# RTM_CON.net
KiCad netlist of a schematic drawn in Altium Designer
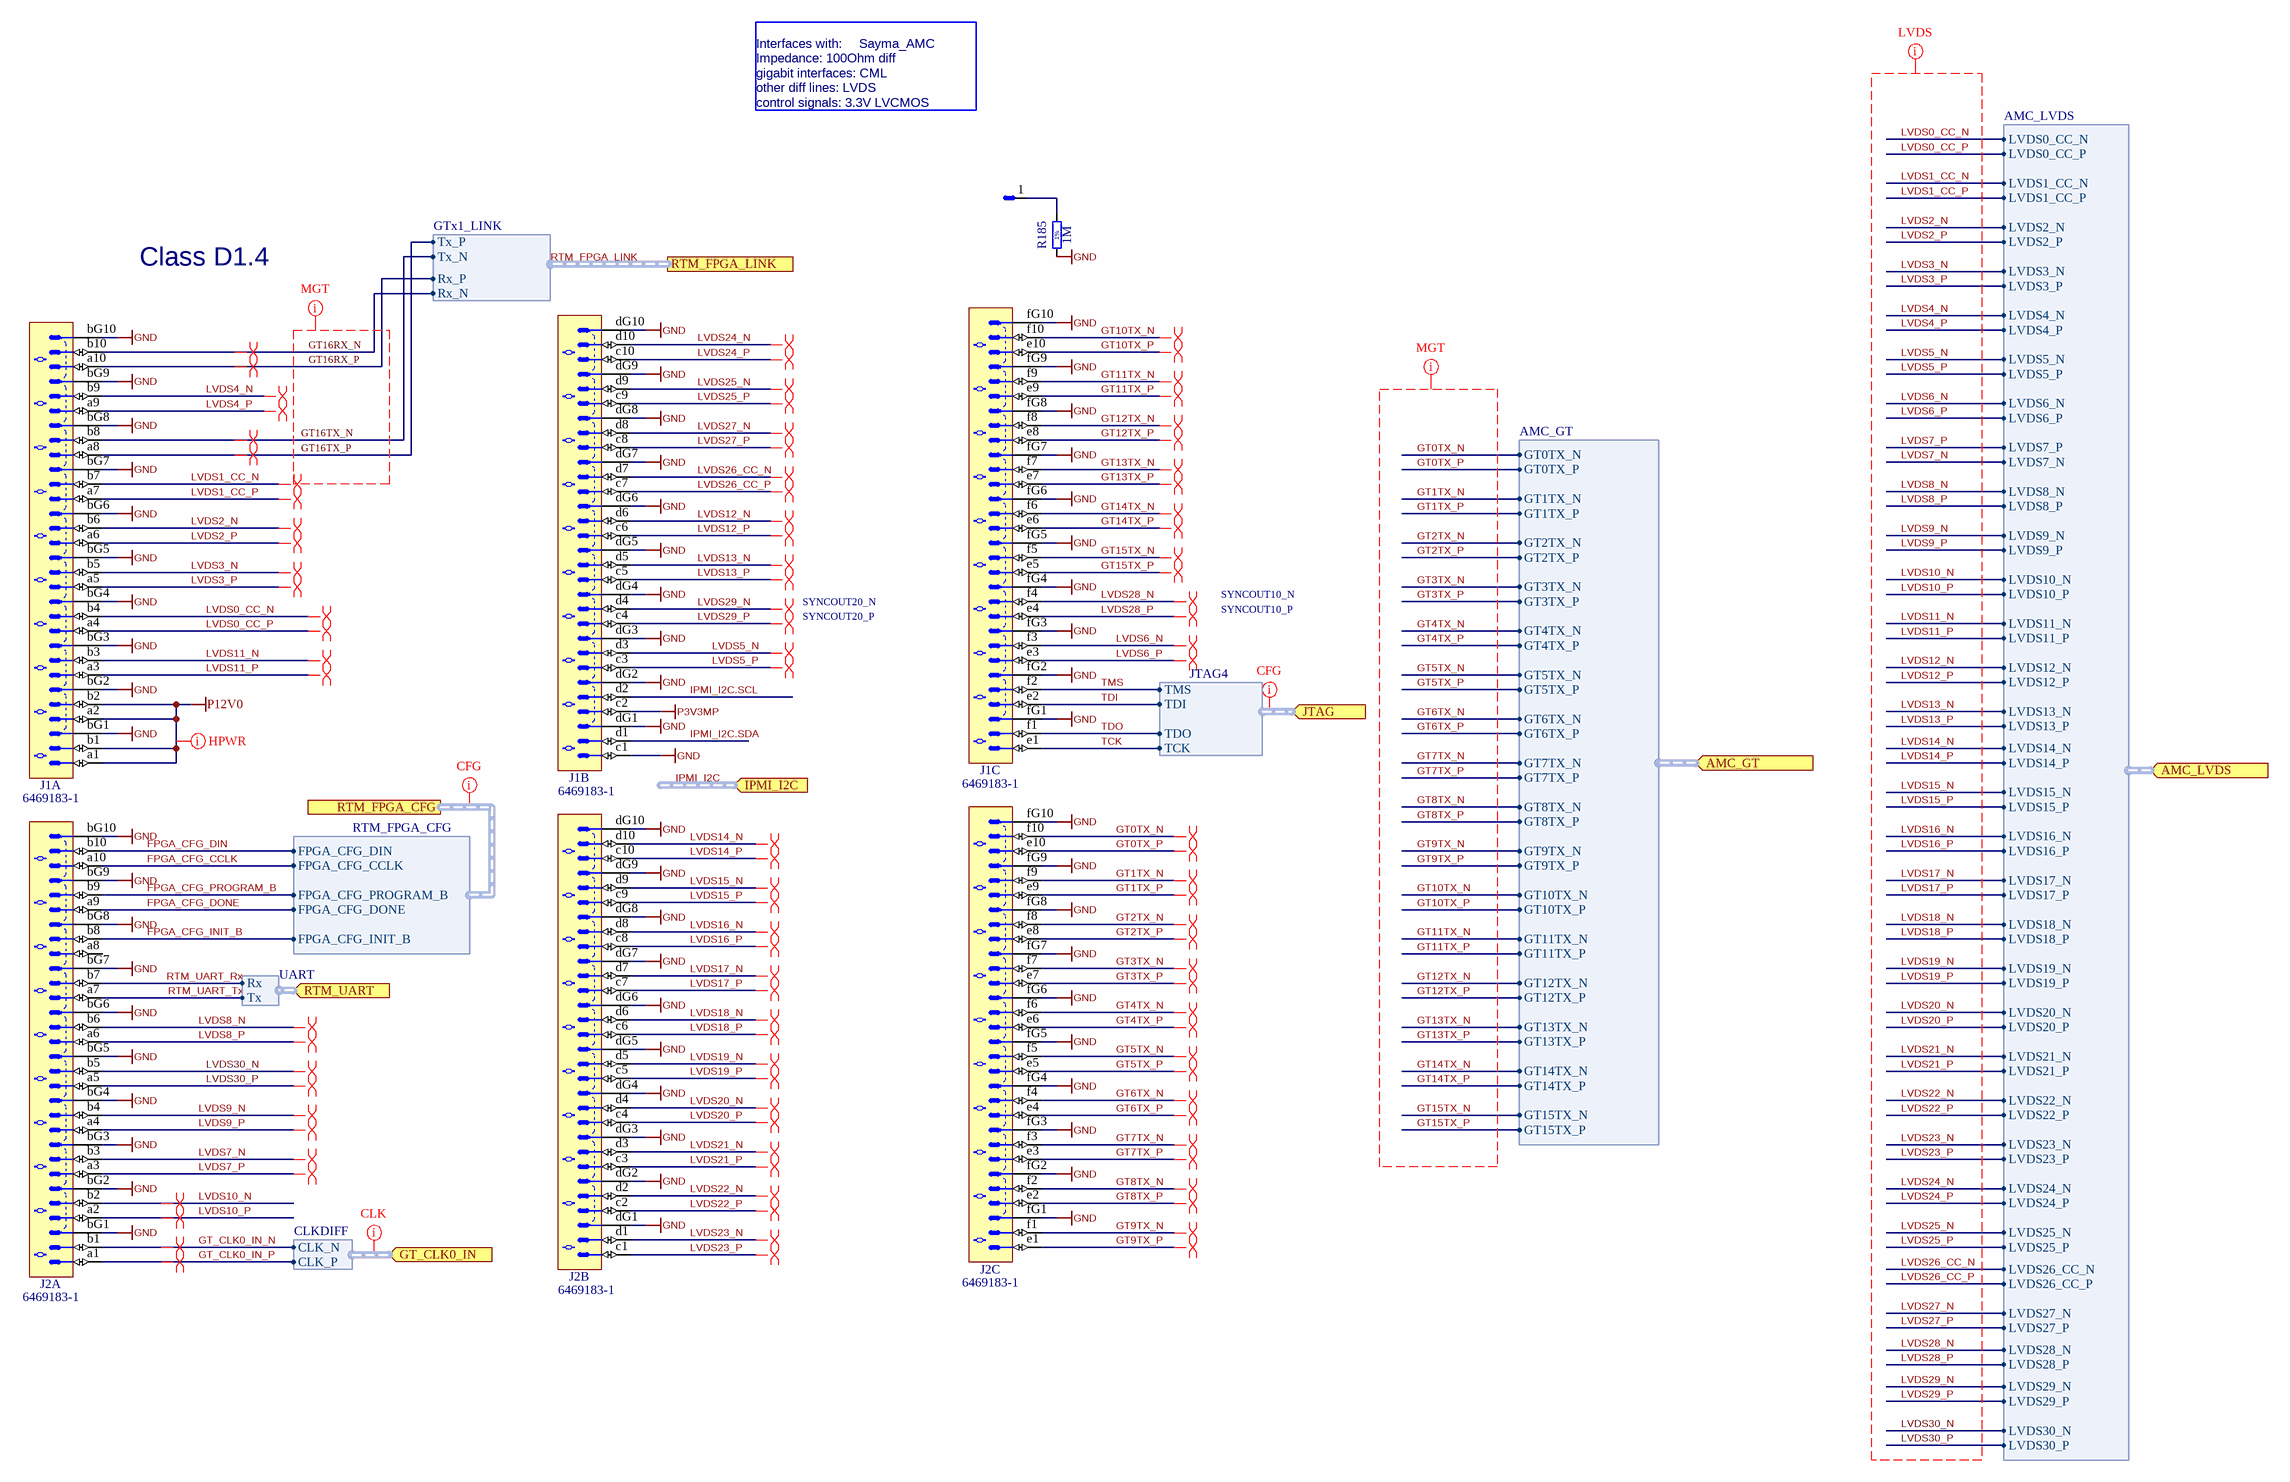
[diagram p0: RTM_CON.SchDoc]

(export (version "E")
  (design (tool "Eeschema 10.0.6"))
  (components
    (comp (ref "J1")
      (value "Advanced TCA")
      (footprint "TYCO_6469183-1")
      (description "Connector 60 ATCA Male 30 Pairs (60 Signals) + 3x10 Ground")
      (fields
        (field (name "MANUFACTURER PART NUMBER") "6469183-1")
        (field (name "MANUFACTURER") "TYCO ELECTRONICS")
        (field (name "PART NUMBER") "TYCO_6469183-1")
        (field (name "AUTHOR") "CERN DEM JLC")
      )
      (libsource (lib "Connectors") (part "Connector ATCA 60+30 Male"))
    )
    (comp (ref "J2")
      (value "Advanced TCA")
      (footprint "TYCO_6469183-1")
      (description "Connector 60 ATCA Male 30 Pairs (60 Signals) + 3x10 Ground")
      (fields
        (field (name "MANUFACTURER PART NUMBER") "6469183-1")
        (field (name "MANUFACTURER") "TYCO ELECTRONICS")
        (field (name "PART NUMBER") "TYCO_6469183-1")
        (field (name "AUTHOR") "CERN DEM JLC")
      )
      (libsource (lib "Connectors") (part "Connector ATCA 60+30 Male"))
    )
    (comp (ref "J3")
      (value "~")
      (footprint "TYCO_1469265-1")
      (description "Single Pin Male")
      (fields
        (field (name "MANUFACTURER PART NUMBER") "1469265-1")
        (field (name "MANUFACTURER") "TYCO ELECTRONICS")
        (field (name "AUTHOR") "CERN DEM JLC")
      )
      (libsource (lib "Connectors") (part "Single Pin Male"))
    )
    (comp (ref "R185")
      (value "1M")
      (footprint "RESC5025X65N")
      (description "Resistor - 1%")
      (fields
        (field (name "MANUFACTURER PART NUMBER") "R2010_1M_1%_0.5W_200PPM")
        (field (name "MANUFACTURER") "GENERIC")
        (field (name "AUTHOR") "CERN DEM JLC")
      )
      (libsource (lib "Resistors") (part "Resistor - 1%"))
    )
  )
  (nets
    (net (code "9") (name "/FPGA_CFG_CCLK") (class "Default")
      (node (ref "J2") (pin "a10") (pinfunction "a10_a10") (pintype "bidirectional"))
    )
    (net (code "10") (name "/FPGA_CFG_DIN") (class "Default")
      (node (ref "J2") (pin "b10") (pinfunction "b10_b10") (pintype "bidirectional"))
    )
    (net (code "11") (name "/FPGA_CFG_DONE") (class "Default")
      (node (ref "J2") (pin "a9") (pinfunction "a9_a9") (pintype "bidirectional"))
    )
    (net (code "12") (name "/FPGA_CFG_INIT_B") (class "Default")
      (node (ref "J2") (pin "b8") (pinfunction "b8_b8") (pintype "bidirectional"))
    )
    (net (code "13") (name "/FPGA_CFG_PROGRAM_B") (class "Default")
      (node (ref "J2") (pin "b9") (pinfunction "b9_b9") (pintype "bidirectional"))
    )
    (net (code "14") (name "/GT0TX_N") (class "Default")
      (node (ref "J2") (pin "f10") (pinfunction "f10_f10") (pintype "bidirectional"))
    )
    (net (code "15") (name "/GT0TX_P") (class "Default")
      (node (ref "J2") (pin "e10") (pinfunction "e10_e10") (pintype "bidirectional"))
    )
    (net (code "16") (name "/GT1TX_N") (class "Default")
      (node (ref "J2") (pin "f9") (pinfunction "f9_f9") (pintype "bidirectional"))
    )
    (net (code "17") (name "/GT1TX_P") (class "Default")
      (node (ref "J2") (pin "e9") (pinfunction "e9_e9") (pintype "bidirectional"))
    )
    (net (code "18") (name "/GT2TX_N") (class "Default")
      (node (ref "J2") (pin "f8") (pinfunction "f8_f8") (pintype "bidirectional"))
    )
    (net (code "19") (name "/GT2TX_P") (class "Default")
      (node (ref "J2") (pin "e8") (pinfunction "e8_e8") (pintype "bidirectional"))
    )
    (net (code "20") (name "/GT3TX_N") (class "Default")
      (node (ref "J2") (pin "f7") (pinfunction "f7_f7") (pintype "bidirectional"))
    )
    (net (code "21") (name "/GT3TX_P") (class "Default")
      (node (ref "J2") (pin "e7") (pinfunction "e7_e7") (pintype "bidirectional"))
    )
    (net (code "22") (name "/GT4TX_N") (class "Default")
      (node (ref "J2") (pin "f6") (pinfunction "f6_f6") (pintype "bidirectional"))
    )
    (net (code "23") (name "/GT4TX_P") (class "Default")
      (node (ref "J2") (pin "e6") (pinfunction "e6_e6") (pintype "bidirectional"))
    )
    (net (code "24") (name "/GT5TX_N") (class "Default")
      (node (ref "J2") (pin "f5") (pinfunction "f5_f5") (pintype "bidirectional"))
    )
    (net (code "25") (name "/GT5TX_P") (class "Default")
      (node (ref "J2") (pin "e5") (pinfunction "e5_e5") (pintype "bidirectional"))
    )
    (net (code "26") (name "/GT6TX_N") (class "Default")
      (node (ref "J2") (pin "f4") (pinfunction "f4_f4") (pintype "bidirectional"))
    )
    (net (code "27") (name "/GT6TX_P") (class "Default")
      (node (ref "J2") (pin "e4") (pinfunction "e4_e4") (pintype "bidirectional"))
    )
    (net (code "28") (name "/GT7TX_N") (class "Default")
      (node (ref "J2") (pin "f3") (pinfunction "f3_f3") (pintype "bidirectional"))
    )
    (net (code "29") (name "/GT7TX_P") (class "Default")
      (node (ref "J2") (pin "e3") (pinfunction "e3_e3") (pintype "bidirectional"))
    )
    (net (code "30") (name "/GT8TX_N") (class "Default")
      (node (ref "J2") (pin "f2") (pinfunction "f2_f2") (pintype "bidirectional"))
    )
    (net (code "31") (name "/GT8TX_P") (class "Default")
      (node (ref "J2") (pin "e2") (pinfunction "e2_e2") (pintype "bidirectional"))
    )
    (net (code "32") (name "/GT9TX_N") (class "Default")
      (node (ref "J2") (pin "f1") (pinfunction "f1_f1") (pintype "bidirectional"))
    )
    (net (code "33") (name "/GT9TX_P") (class "Default")
      (node (ref "J2") (pin "e1") (pinfunction "e1_e1") (pintype "bidirectional"))
    )
    (net (code "34") (name "/GT10TX_N") (class "Default")
      (node (ref "J1") (pin "f10") (pinfunction "f10_f10") (pintype "bidirectional"))
    )
    (net (code "35") (name "/GT10TX_P") (class "Default")
      (node (ref "J1") (pin "e10") (pinfunction "e10_e10") (pintype "bidirectional"))
    )
    (net (code "36") (name "/GT11TX_N") (class "Default")
      (node (ref "J1") (pin "f9") (pinfunction "f9_f9") (pintype "bidirectional"))
    )
    (net (code "37") (name "/GT11TX_P") (class "Default")
      (node (ref "J1") (pin "e9") (pinfunction "e9_e9") (pintype "bidirectional"))
    )
    (net (code "38") (name "/GT12TX_N") (class "Default")
      (node (ref "J1") (pin "f8") (pinfunction "f8_f8") (pintype "bidirectional"))
    )
    (net (code "39") (name "/GT12TX_P") (class "Default")
      (node (ref "J1") (pin "e8") (pinfunction "e8_e8") (pintype "bidirectional"))
    )
    (net (code "40") (name "/GT13TX_N") (class "Default")
      (node (ref "J1") (pin "f7") (pinfunction "f7_f7") (pintype "bidirectional"))
    )
    (net (code "41") (name "/GT13TX_P") (class "Default")
      (node (ref "J1") (pin "e7") (pinfunction "e7_e7") (pintype "bidirectional"))
    )
    (net (code "42") (name "/GT14TX_N") (class "Default")
      (node (ref "J1") (pin "f6") (pinfunction "f6_f6") (pintype "bidirectional"))
    )
    (net (code "43") (name "/GT14TX_P") (class "Default")
      (node (ref "J1") (pin "e6") (pinfunction "e6_e6") (pintype "bidirectional"))
    )
    (net (code "44") (name "/GT15TX_N") (class "Default")
      (node (ref "J1") (pin "f5") (pinfunction "f5_f5") (pintype "bidirectional"))
    )
    (net (code "45") (name "/GT15TX_P") (class "Default")
      (node (ref "J1") (pin "e5") (pinfunction "e5_e5") (pintype "bidirectional"))
    )
    (net (code "46") (name "/GT16RX_N") (class "Default")
      (node (ref "J1") (pin "b10") (pinfunction "b10_b10") (pintype "bidirectional"))
    )
    (net (code "47") (name "/GT16RX_P") (class "Default")
      (node (ref "J1") (pin "a10") (pinfunction "a10_a10") (pintype "bidirectional"))
    )
    (net (code "48") (name "/GT16TX_N") (class "Default")
      (node (ref "J1") (pin "b8") (pinfunction "b8_b8") (pintype "bidirectional"))
    )
    (net (code "49") (name "/GT16TX_P") (class "Default")
      (node (ref "J1") (pin "a8") (pinfunction "a8_a8") (pintype "bidirectional"))
    )
    (net (code "50") (name "/GT_CLK0_IN_N") (class "Default")
      (node (ref "J2") (pin "b1") (pinfunction "b1_b1") (pintype "bidirectional"))
    )
    (net (code "51") (name "/GT_CLK0_IN_P") (class "Default")
      (node (ref "J2") (pin "a1") (pinfunction "a1_a1") (pintype "bidirectional"))
    )
    (net (code "52") (name "/IPMI_I2C.SCL") (class "Default")
      (node (ref "J1") (pin "d2") (pinfunction "d2_d2") (pintype "bidirectional"))
    )
    (net (code "53") (name "/IPMI_I2C.SDA") (class "Default")
      (node (ref "J1") (pin "d1") (pinfunction "d1_d1") (pintype "bidirectional"))
    )
    (net (code "54") (name "/LVDS0_CC_N") (class "Default")
      (node (ref "J1") (pin "b4") (pinfunction "b4_b4") (pintype "bidirectional"))
    )
    (net (code "55") (name "/LVDS0_CC_P") (class "Default")
      (node (ref "J1") (pin "a4") (pinfunction "a4_a4") (pintype "bidirectional"))
    )
    (net (code "56") (name "/LVDS1_CC_N") (class "Default")
      (node (ref "J1") (pin "b7") (pinfunction "b7_b7") (pintype "bidirectional"))
    )
    (net (code "57") (name "/LVDS1_CC_P") (class "Default")
      (node (ref "J1") (pin "a7") (pinfunction "a7_a7") (pintype "bidirectional"))
    )
    (net (code "58") (name "/LVDS2_N") (class "Default")
      (node (ref "J1") (pin "b6") (pinfunction "b6_b6") (pintype "bidirectional"))
    )
    (net (code "59") (name "/LVDS2_P") (class "Default")
      (node (ref "J1") (pin "a6") (pinfunction "a6_a6") (pintype "bidirectional"))
    )
    (net (code "60") (name "/LVDS3_N") (class "Default")
      (node (ref "J1") (pin "b5") (pinfunction "b5_b5") (pintype "bidirectional"))
    )
    (net (code "61") (name "/LVDS3_P") (class "Default")
      (node (ref "J1") (pin "a5") (pinfunction "a5_a5") (pintype "bidirectional"))
    )
    (net (code "62") (name "/LVDS4_N") (class "Default")
      (node (ref "J1") (pin "b9") (pinfunction "b9_b9") (pintype "bidirectional"))
    )
    (net (code "63") (name "/LVDS4_P") (class "Default")
      (node (ref "J1") (pin "a9") (pinfunction "a9_a9") (pintype "bidirectional"))
    )
    (net (code "64") (name "/LVDS5_N") (class "Default")
      (node (ref "J1") (pin "d3") (pinfunction "d3_d3") (pintype "bidirectional"))
    )
    (net (code "65") (name "/LVDS5_P") (class "Default")
      (node (ref "J1") (pin "c3") (pinfunction "c3_c3") (pintype "bidirectional"))
    )
    (net (code "66") (name "/LVDS6_N") (class "Default")
      (node (ref "J1") (pin "f3") (pinfunction "f3_f3") (pintype "bidirectional"))
    )
    (net (code "67") (name "/LVDS6_P") (class "Default")
      (node (ref "J1") (pin "e3") (pinfunction "e3_e3") (pintype "bidirectional"))
    )
    (net (code "68") (name "/LVDS7_N") (class "Default")
      (node (ref "J2") (pin "b3") (pinfunction "b3_b3") (pintype "bidirectional"))
    )
    (net (code "69") (name "/LVDS7_P") (class "Default")
      (node (ref "J2") (pin "a3") (pinfunction "a3_a3") (pintype "bidirectional"))
    )
    (net (code "70") (name "/LVDS8_N") (class "Default")
      (node (ref "J2") (pin "b6") (pinfunction "b6_b6") (pintype "bidirectional"))
    )
    (net (code "71") (name "/LVDS8_P") (class "Default")
      (node (ref "J2") (pin "a6") (pinfunction "a6_a6") (pintype "bidirectional"))
    )
    (net (code "72") (name "/LVDS9_N") (class "Default")
      (node (ref "J2") (pin "b4") (pinfunction "b4_b4") (pintype "bidirectional"))
    )
    (net (code "73") (name "/LVDS9_P") (class "Default")
      (node (ref "J2") (pin "a4") (pinfunction "a4_a4") (pintype "bidirectional"))
    )
    (net (code "74") (name "/LVDS10_N") (class "Default")
      (node (ref "J2") (pin "b2") (pinfunction "b2_b2") (pintype "bidirectional"))
    )
    (net (code "75") (name "/LVDS10_P") (class "Default")
      (node (ref "J2") (pin "a2") (pinfunction "a2_a2") (pintype "bidirectional"))
    )
    (net (code "76") (name "/LVDS11_N") (class "Default")
      (node (ref "J1") (pin "b3") (pinfunction "b3_b3") (pintype "bidirectional"))
    )
    (net (code "77") (name "/LVDS11_P") (class "Default")
      (node (ref "J1") (pin "a3") (pinfunction "a3_a3") (pintype "bidirectional"))
    )
    (net (code "78") (name "/LVDS12_N") (class "Default")
      (node (ref "J1") (pin "d6") (pinfunction "d6_d6") (pintype "bidirectional"))
    )
    (net (code "79") (name "/LVDS12_P") (class "Default")
      (node (ref "J1") (pin "c6") (pinfunction "c6_c6") (pintype "bidirectional"))
    )
    (net (code "80") (name "/LVDS13_N") (class "Default")
      (node (ref "J1") (pin "d5") (pinfunction "d5_d5") (pintype "bidirectional"))
    )
    (net (code "81") (name "/LVDS13_P") (class "Default")
      (node (ref "J1") (pin "c5") (pinfunction "c5_c5") (pintype "bidirectional"))
    )
    (net (code "82") (name "/LVDS14_N") (class "Default")
      (node (ref "J2") (pin "d10") (pinfunction "d10_d10") (pintype "bidirectional"))
    )
    (net (code "83") (name "/LVDS14_P") (class "Default")
      (node (ref "J2") (pin "c10") (pinfunction "c10_c10") (pintype "bidirectional"))
    )
    (net (code "84") (name "/LVDS15_N") (class "Default")
      (node (ref "J2") (pin "d9") (pinfunction "d9_d9") (pintype "bidirectional"))
    )
    (net (code "85") (name "/LVDS15_P") (class "Default")
      (node (ref "J2") (pin "c9") (pinfunction "c9_c9") (pintype "bidirectional"))
    )
    (net (code "86") (name "/LVDS16_N") (class "Default")
      (node (ref "J2") (pin "d8") (pinfunction "d8_d8") (pintype "bidirectional"))
    )
    (net (code "87") (name "/LVDS16_P") (class "Default")
      (node (ref "J2") (pin "c8") (pinfunction "c8_c8") (pintype "bidirectional"))
    )
    (net (code "88") (name "/LVDS17_N") (class "Default")
      (node (ref "J2") (pin "d7") (pinfunction "d7_d7") (pintype "bidirectional"))
    )
    (net (code "89") (name "/LVDS17_P") (class "Default")
      (node (ref "J2") (pin "c7") (pinfunction "c7_c7") (pintype "bidirectional"))
    )
    (net (code "90") (name "/LVDS18_N") (class "Default")
      (node (ref "J2") (pin "d6") (pinfunction "d6_d6") (pintype "bidirectional"))
    )
    (net (code "91") (name "/LVDS18_P") (class "Default")
      (node (ref "J2") (pin "c6") (pinfunction "c6_c6") (pintype "bidirectional"))
    )
    (net (code "92") (name "/LVDS19_N") (class "Default")
      (node (ref "J2") (pin "d5") (pinfunction "d5_d5") (pintype "bidirectional"))
    )
    (net (code "93") (name "/LVDS19_P") (class "Default")
      (node (ref "J2") (pin "c5") (pinfunction "c5_c5") (pintype "bidirectional"))
    )
    (net (code "94") (name "/LVDS20_N") (class "Default")
      (node (ref "J2") (pin "d4") (pinfunction "d4_d4") (pintype "bidirectional"))
    )
    (net (code "95") (name "/LVDS20_P") (class "Default")
      (node (ref "J2") (pin "c4") (pinfunction "c4_c4") (pintype "bidirectional"))
    )
    (net (code "96") (name "/LVDS21_N") (class "Default")
      (node (ref "J2") (pin "d3") (pinfunction "d3_d3") (pintype "bidirectional"))
    )
    (net (code "97") (name "/LVDS21_P") (class "Default")
      (node (ref "J2") (pin "c3") (pinfunction "c3_c3") (pintype "bidirectional"))
    )
    (net (code "98") (name "/LVDS22_N") (class "Default")
      (node (ref "J2") (pin "d2") (pinfunction "d2_d2") (pintype "bidirectional"))
    )
    (net (code "99") (name "/LVDS22_P") (class "Default")
      (node (ref "J2") (pin "c2") (pinfunction "c2_c2") (pintype "bidirectional"))
    )
    (net (code "100") (name "/LVDS23_N") (class "Default")
      (node (ref "J2") (pin "d1") (pinfunction "d1_d1") (pintype "bidirectional"))
    )
    (net (code "101") (name "/LVDS23_P") (class "Default")
      (node (ref "J2") (pin "c1") (pinfunction "c1_c1") (pintype "bidirectional"))
    )
    (net (code "102") (name "/LVDS24_N") (class "Default")
      (node (ref "J1") (pin "d10") (pinfunction "d10_d10") (pintype "bidirectional"))
    )
    (net (code "103") (name "/LVDS24_P") (class "Default")
      (node (ref "J1") (pin "c10") (pinfunction "c10_c10") (pintype "bidirectional"))
    )
    (net (code "104") (name "/LVDS25_N") (class "Default")
      (node (ref "J1") (pin "d9") (pinfunction "d9_d9") (pintype "bidirectional"))
    )
    (net (code "105") (name "/LVDS25_P") (class "Default")
      (node (ref "J1") (pin "c9") (pinfunction "c9_c9") (pintype "bidirectional"))
    )
    (net (code "106") (name "/LVDS26_CC_N") (class "Default")
      (node (ref "J1") (pin "d7") (pinfunction "d7_d7") (pintype "bidirectional"))
    )
    (net (code "107") (name "/LVDS26_CC_P") (class "Default")
      (node (ref "J1") (pin "c7") (pinfunction "c7_c7") (pintype "bidirectional"))
    )
    (net (code "108") (name "/LVDS27_N") (class "Default")
      (node (ref "J1") (pin "d8") (pinfunction "d8_d8") (pintype "bidirectional"))
    )
    (net (code "109") (name "/LVDS27_P") (class "Default")
      (node (ref "J1") (pin "c8") (pinfunction "c8_c8") (pintype "bidirectional"))
    )
    (net (code "110") (name "/LVDS28_N") (class "Default")
      (node (ref "J1") (pin "f4") (pinfunction "f4_f4") (pintype "bidirectional"))
    )
    (net (code "111") (name "/LVDS28_P") (class "Default")
      (node (ref "J1") (pin "e4") (pinfunction "e4_e4") (pintype "bidirectional"))
    )
    (net (code "112") (name "/LVDS29_N") (class "Default")
      (node (ref "J1") (pin "d4") (pinfunction "d4_d4") (pintype "bidirectional"))
    )
    (net (code "113") (name "/LVDS29_P") (class "Default")
      (node (ref "J1") (pin "c4") (pinfunction "c4_c4") (pintype "bidirectional"))
    )
    (net (code "114") (name "/LVDS30_N") (class "Default")
      (node (ref "J2") (pin "b5") (pinfunction "b5_b5") (pintype "bidirectional"))
    )
    (net (code "115") (name "/LVDS30_P") (class "Default")
      (node (ref "J2") (pin "a5") (pinfunction "a5_a5") (pintype "bidirectional"))
    )
    (net (code "117") (name "/RTM_UART_Rx") (class "Default")
      (node (ref "J2") (pin "b7") (pinfunction "b7_b7") (pintype "bidirectional"))
    )
    (net (code "118") (name "/RTM_UART_Tx") (class "Default")
      (node (ref "J2") (pin "a7") (pinfunction "a7_a7") (pintype "bidirectional"))
    )
    (net (code "119") (name "/TCK") (class "Default")
      (node (ref "J1") (pin "e1") (pinfunction "e1_e1") (pintype "bidirectional"))
    )
    (net (code "120") (name "/TDI") (class "Default")
      (node (ref "J1") (pin "e2") (pinfunction "e2_e2") (pintype "bidirectional"))
    )
    (net (code "121") (name "/TDO") (class "Default")
      (node (ref "J1") (pin "f1") (pinfunction "f1_f1") (pintype "bidirectional"))
    )
    (net (code "122") (name "/TMS") (class "Default")
      (node (ref "J1") (pin "f2") (pinfunction "f2_f2") (pintype "bidirectional"))
    )
    (net (code "130") (name "GND") (class "Default")
      (node (ref "J1") (pin "bG1") (pinfunction "bG1_bG1") (pintype "power_in"))
      (node (ref "J1") (pin "bG10") (pinfunction "bG10_bG10") (pintype "power_in"))
      (node (ref "J1") (pin "bG2") (pinfunction "bG2_bG2") (pintype "power_in"))
      (node (ref "J1") (pin "bG3") (pinfunction "bG3_bG3") (pintype "power_in"))
      (node (ref "J1") (pin "bG4") (pinfunction "bG4_bG4") (pintype "power_in"))
      (node (ref "J1") (pin "bG5") (pinfunction "bG5_bG5") (pintype "power_in"))
      (node (ref "J1") (pin "bG6") (pinfunction "bG6_bG6") (pintype "power_in"))
      (node (ref "J1") (pin "bG7") (pinfunction "bG7_bG7") (pintype "power_in"))
      (node (ref "J1") (pin "bG8") (pinfunction "bG8_bG8") (pintype "power_in"))
      (node (ref "J1") (pin "bG9") (pinfunction "bG9_bG9") (pintype "power_in"))
      (node (ref "J1") (pin "c1") (pinfunction "c1_c1") (pintype "bidirectional"))
      (node (ref "J1") (pin "dG1") (pinfunction "dG1_dG1") (pintype "power_in"))
      (node (ref "J1") (pin "dG10") (pinfunction "dG10_dG10") (pintype "power_in"))
      (node (ref "J1") (pin "dG2") (pinfunction "dG2_dG2") (pintype "power_in"))
      (node (ref "J1") (pin "dG3") (pinfunction "dG3_dG3") (pintype "power_in"))
      (node (ref "J1") (pin "dG4") (pinfunction "dG4_dG4") (pintype "power_in"))
      (node (ref "J1") (pin "dG5") (pinfunction "dG5_dG5") (pintype "power_in"))
      (node (ref "J1") (pin "dG6") (pinfunction "dG6_dG6") (pintype "power_in"))
      (node (ref "J1") (pin "dG7") (pinfunction "dG7_dG7") (pintype "power_in"))
      (node (ref "J1") (pin "dG8") (pinfunction "dG8_dG8") (pintype "power_in"))
      (node (ref "J1") (pin "dG9") (pinfunction "dG9_dG9") (pintype "power_in"))
      (node (ref "J1") (pin "fG1") (pinfunction "fG1_fG1") (pintype "power_in"))
      (node (ref "J1") (pin "fG10") (pinfunction "fG10_fG10") (pintype "power_in"))
      (node (ref "J1") (pin "fG2") (pinfunction "fG2_fG2") (pintype "power_in"))
      (node (ref "J1") (pin "fG3") (pinfunction "fG3_fG3") (pintype "power_in"))
      (node (ref "J1") (pin "fG4") (pinfunction "fG4_fG4") (pintype "power_in"))
      (node (ref "J1") (pin "fG5") (pinfunction "fG5_fG5") (pintype "power_in"))
      (node (ref "J1") (pin "fG6") (pinfunction "fG6_fG6") (pintype "power_in"))
      (node (ref "J1") (pin "fG7") (pinfunction "fG7_fG7") (pintype "power_in"))
      (node (ref "J1") (pin "fG8") (pinfunction "fG8_fG8") (pintype "power_in"))
      (node (ref "J1") (pin "fG9") (pinfunction "fG9_fG9") (pintype "power_in"))
      (node (ref "J2") (pin "bG1") (pinfunction "bG1_bG1") (pintype "power_in"))
      (node (ref "J2") (pin "bG10") (pinfunction "bG10_bG10") (pintype "power_in"))
      (node (ref "J2") (pin "bG2") (pinfunction "bG2_bG2") (pintype "power_in"))
      (node (ref "J2") (pin "bG3") (pinfunction "bG3_bG3") (pintype "power_in"))
      (node (ref "J2") (pin "bG4") (pinfunction "bG4_bG4") (pintype "power_in"))
      (node (ref "J2") (pin "bG5") (pinfunction "bG5_bG5") (pintype "power_in"))
      (node (ref "J2") (pin "bG6") (pinfunction "bG6_bG6") (pintype "power_in"))
      (node (ref "J2") (pin "bG7") (pinfunction "bG7_bG7") (pintype "power_in"))
      (node (ref "J2") (pin "bG8") (pinfunction "bG8_bG8") (pintype "power_in"))
      (node (ref "J2") (pin "bG9") (pinfunction "bG9_bG9") (pintype "power_in"))
      (node (ref "J2") (pin "dG1") (pinfunction "dG1_dG1") (pintype "power_in"))
      (node (ref "J2") (pin "dG10") (pinfunction "dG10_dG10") (pintype "power_in"))
      (node (ref "J2") (pin "dG2") (pinfunction "dG2_dG2") (pintype "power_in"))
      (node (ref "J2") (pin "dG3") (pinfunction "dG3_dG3") (pintype "power_in"))
      (node (ref "J2") (pin "dG4") (pinfunction "dG4_dG4") (pintype "power_in"))
      (node (ref "J2") (pin "dG5") (pinfunction "dG5_dG5") (pintype "power_in"))
      (node (ref "J2") (pin "dG6") (pinfunction "dG6_dG6") (pintype "power_in"))
      (node (ref "J2") (pin "dG7") (pinfunction "dG7_dG7") (pintype "power_in"))
      (node (ref "J2") (pin "dG8") (pinfunction "dG8_dG8") (pintype "power_in"))
      (node (ref "J2") (pin "dG9") (pinfunction "dG9_dG9") (pintype "power_in"))
      (node (ref "J2") (pin "fG1") (pinfunction "fG1_fG1") (pintype "power_in"))
      (node (ref "J2") (pin "fG10") (pinfunction "fG10_fG10") (pintype "power_in"))
      (node (ref "J2") (pin "fG2") (pinfunction "fG2_fG2") (pintype "power_in"))
      (node (ref "J2") (pin "fG3") (pinfunction "fG3_fG3") (pintype "power_in"))
      (node (ref "J2") (pin "fG4") (pinfunction "fG4_fG4") (pintype "power_in"))
      (node (ref "J2") (pin "fG5") (pinfunction "fG5_fG5") (pintype "power_in"))
      (node (ref "J2") (pin "fG6") (pinfunction "fG6_fG6") (pintype "power_in"))
      (node (ref "J2") (pin "fG7") (pinfunction "fG7_fG7") (pintype "power_in"))
      (node (ref "J2") (pin "fG8") (pinfunction "fG8_fG8") (pintype "power_in"))
      (node (ref "J2") (pin "fG9") (pinfunction "fG9_fG9") (pintype "power_in"))
      (node (ref "R185") (pin "1") (pinfunction "1_1") (pintype "passive"))
    )
    (net (code "131") (name "Net-(J3-Pad1)") (class "Default")
      (node (ref "J3") (pin "1") (pinfunction "1_1") (pintype "bidirectional"))
      (node (ref "R185") (pin "2") (pinfunction "2_2") (pintype "passive"))
    )
    (net (code "132") (name "P3V3MP") (class "Default")
      (node (ref "J1") (pin "c2") (pinfunction "c2_c2") (pintype "bidirectional"))
    )
    (net (code "133") (name "P12V0") (class "Default")
      (node (ref "J1") (pin "a1") (pinfunction "a1_a1") (pintype "bidirectional"))
      (node (ref "J1") (pin "a2") (pinfunction "a2_a2") (pintype "bidirectional"))
      (node (ref "J1") (pin "b1") (pinfunction "b1_b1") (pintype "bidirectional"))
      (node (ref "J1") (pin "b2") (pinfunction "b2_b2") (pintype "bidirectional"))
    )
    (net (code "134") (name "unconnected-(J2-Pada8)") (class "Default")
      (node (ref "J2") (pin "a8") (pinfunction "a8_a8") (pintype "bidirectional"))
    )
  )
)
